# untitled.net
KiCad netlist of a schematic drawn in EAGLE
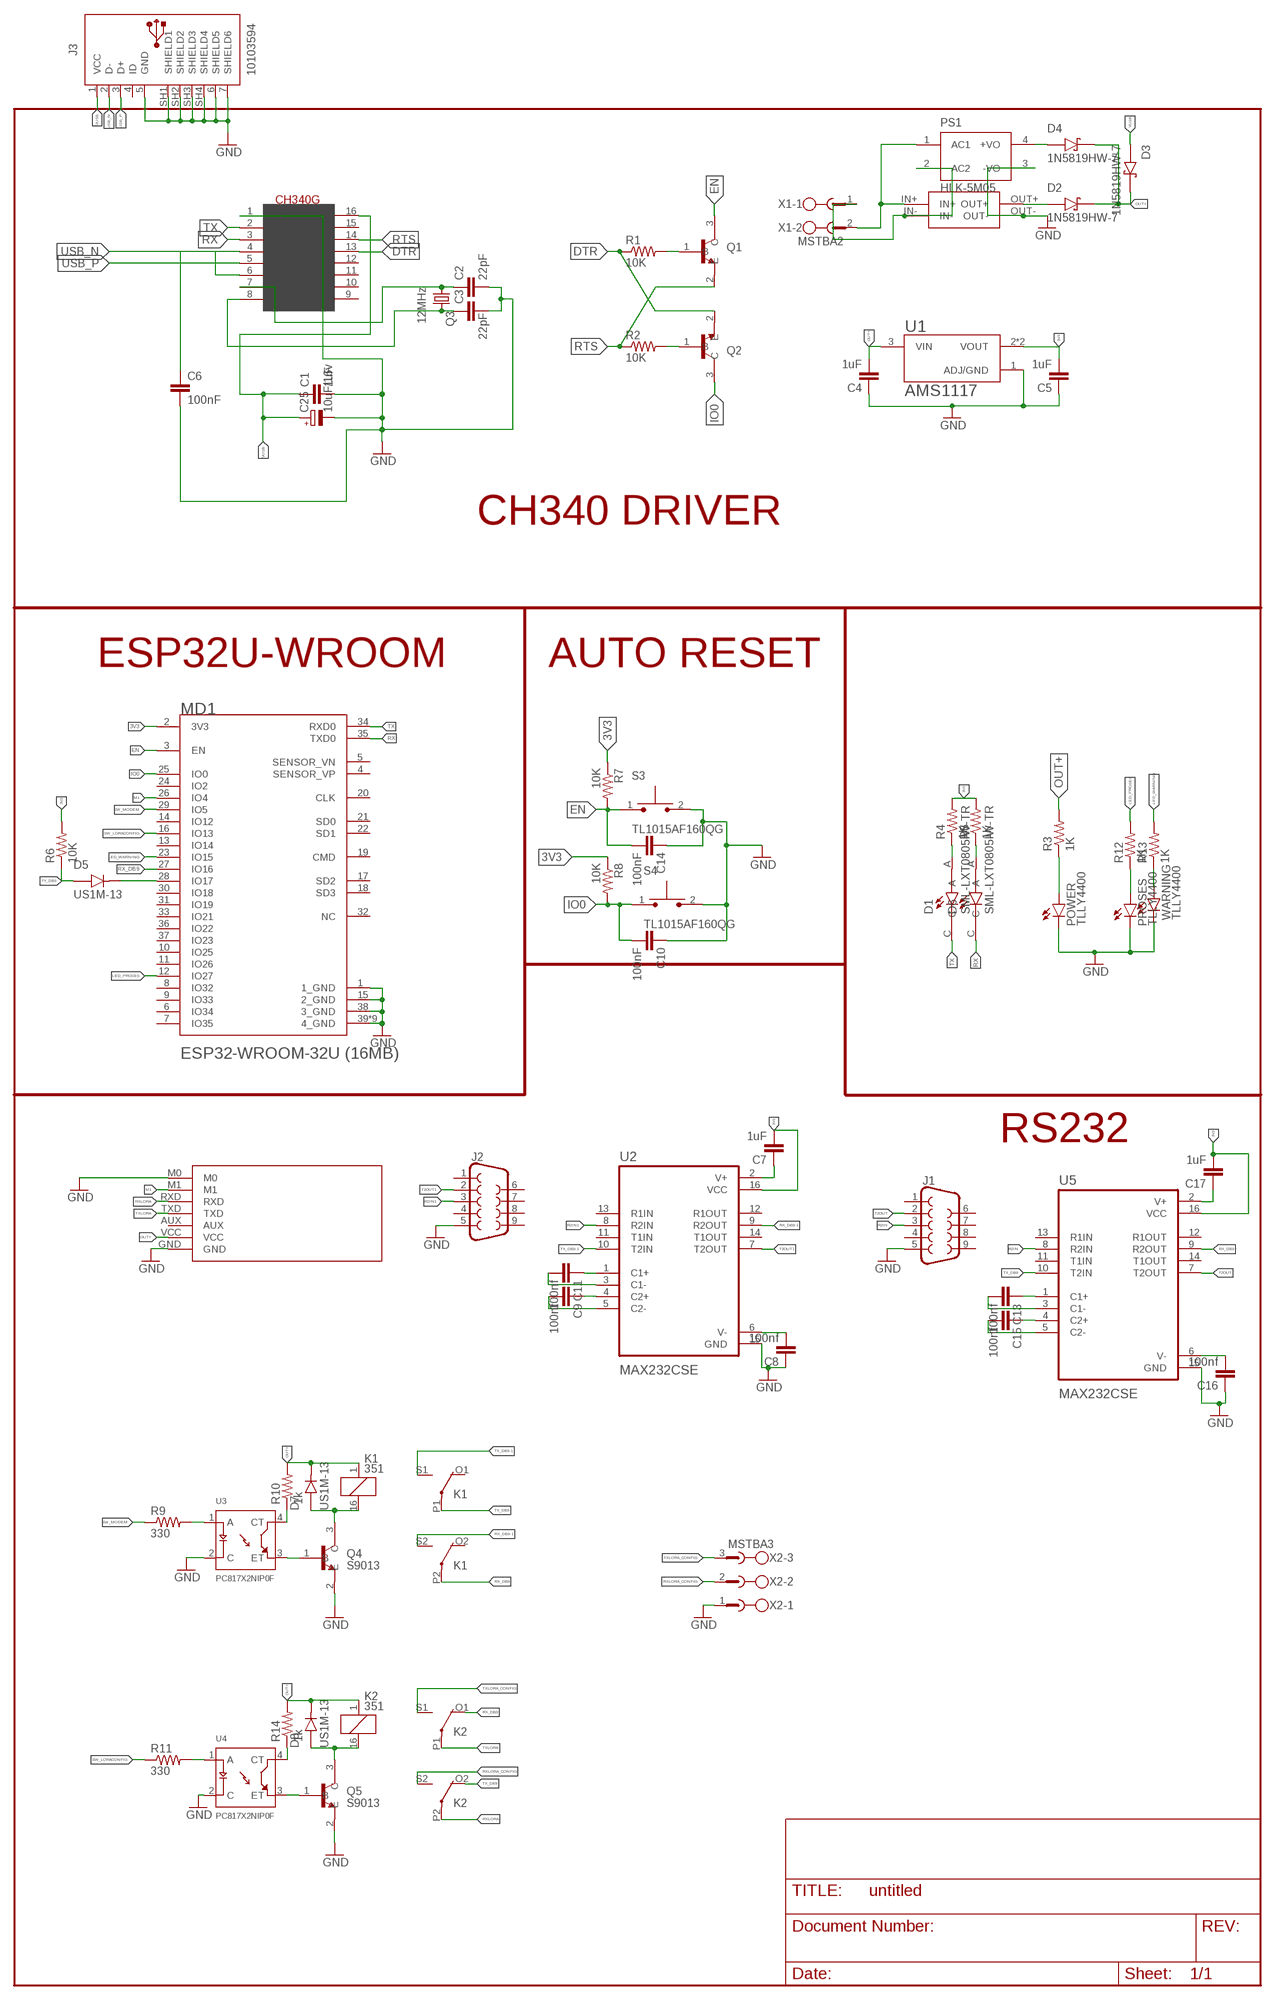
[diagram p0: schematic, sheet 1]

(export (version "E")
  (design (tool "Eeschema 10.0.6"))
  (components
    (comp (ref "C1")
      (value "1uF")
      (footprint "eagle-import:C0805K")
      (libsource (lib "eagle-import") (part "C-EUC0805K"))
    )
    (comp (ref "C2")
      (value "22pF")
      (footprint "eagle-import:C0805K")
      (libsource (lib "eagle-import") (part "C-EUC0805K"))
    )
    (comp (ref "C3")
      (value "22pF")
      (footprint "eagle-import:C0805K")
      (libsource (lib "eagle-import") (part "C-EUC0805K"))
    )
    (comp (ref "C4")
      (value "1uF")
      (footprint "eagle-import:C0805K")
      (libsource (lib "eagle-import") (part "C-EUC0805K"))
    )
    (comp (ref "C5")
      (value "1uF")
      (footprint "eagle-import:C0805K")
      (libsource (lib "eagle-import") (part "C-EUC0805K"))
    )
    (comp (ref "C6")
      (value "100nF")
      (footprint "eagle-import:C0805K")
      (libsource (lib "eagle-import") (part "C-EUC0805K"))
    )
    (comp (ref "C7")
      (value "1uF")
      (footprint "eagle-import:C0805")
      (libsource (lib "eagle-import") (part "C-EUC0805"))
    )
    (comp (ref "C8")
      (value "100nf")
      (footprint "eagle-import:C0805")
      (libsource (lib "eagle-import") (part "C-EUC0805"))
    )
    (comp (ref "C9")
      (value "100nf")
      (footprint "eagle-import:C0805")
      (libsource (lib "eagle-import") (part "C-EUC0805"))
    )
    (comp (ref "C10")
      (value "100nF")
      (footprint "eagle-import:C0805K")
      (libsource (lib "eagle-import") (part "C-EUC0805K"))
    )
    (comp (ref "C11")
      (value "100nf")
      (footprint "eagle-import:C0805")
      (libsource (lib "eagle-import") (part "C-EUC0805"))
    )
    (comp (ref "C13")
      (value "100nf")
      (footprint "eagle-import:C0805")
      (libsource (lib "eagle-import") (part "C-EUC0805"))
    )
    (comp (ref "C14")
      (value "100nF")
      (footprint "eagle-import:C0805K")
      (libsource (lib "eagle-import") (part "C-EUC0805K"))
    )
    (comp (ref "C15")
      (value "100nf")
      (footprint "eagle-import:C0805")
      (libsource (lib "eagle-import") (part "C-EUC0805"))
    )
    (comp (ref "C16")
      (value "100nf")
      (footprint "eagle-import:C0805")
      (libsource (lib "eagle-import") (part "C-EUC0805"))
    )
    (comp (ref "C17")
      (value "1uF")
      (footprint "eagle-import:C0805")
      (libsource (lib "eagle-import") (part "C-EUC0805"))
    )
    (comp (ref "C25")
      (value "10uF/16v")
      (footprint "eagle-import:153CLV-0505")
      (libsource (lib "eagle-import") (part "CPOL-EU153CLV-0505"))
    )
    (comp (ref "D1")
      (value "SML-LXT0805IW-TR")
      (footprint "eagle-import:LEDC2012X120N")
      (fields (field (name "MF") "Lumex Opto/Components"))
      (libsource (lib "eagle-import") (part "SML-LXT0805IW-TR"))
    )
    (comp (ref "D2")
      (value "1N5819HW-7")
      (footprint "eagle-import:SOD3715X145N")
      (fields (field (name "MF") "Diodes Inc."))
      (libsource (lib "eagle-import") (part "1N5819HW-7"))
    )
    (comp (ref "D3")
      (value "1N5819HW-7")
      (footprint "eagle-import:SOD3715X145N")
      (fields (field (name "MF") "Diodes Inc."))
      (libsource (lib "eagle-import") (part "1N5819HW-7"))
    )
    (comp (ref "D4")
      (value "1N5819HW-7")
      (footprint "eagle-import:SOD3715X145N")
      (fields (field (name "MF") "Diodes Inc."))
      (libsource (lib "eagle-import") (part "1N5819HW-7"))
    )
    (comp (ref "D5")
      (value "US1M-13")
      (footprint "eagle-import:DIOM5226X240N")
      (fields (field (name "MF") "Diodes Incorporated"))
      (libsource (lib "eagle-import") (part "US1M-13"))
    )
    (comp (ref "D6")
      (value "SML-LXT0805IW-TR")
      (footprint "eagle-import:LEDC2012X120N")
      (fields (field (name "MF") "Lumex Opto/Components"))
      (libsource (lib "eagle-import") (part "SML-LXT0805IW-TR"))
    )
    (comp (ref "D7")
      (value "US1M-13")
      (footprint "eagle-import:DIOM5226X240N")
      (fields (field (name "MF") "Diodes Incorporated"))
      (libsource (lib "eagle-import") (part "US1M-13"))
    )
    (comp (ref "D8")
      (value "US1M-13")
      (footprint "eagle-import:DIOM5226X240N")
      (fields (field (name "MF") "Diodes Incorporated"))
      (libsource (lib "eagle-import") (part "US1M-13"))
    )
    (comp (ref "EBYTEE220-900T22D1")
      (value "EBYTEE220-900T22D")
      (footprint "eagle-import:EBYTEE220-900T22D")
      (libsource (lib "eagle-import") (part "EBYTEE220-900T22D"))
    )
    (comp (ref "J1")
      (value "DB9MALE")
      (footprint "eagle-import:DB9_MALE")
      (libsource (lib "eagle-import") (part "DB9MALE"))
    )
    (comp (ref "J2")
      (value "DB9MALE")
      (footprint "eagle-import:DB9_MALE")
      (libsource (lib "eagle-import") (part "DB9MALE"))
    )
    (comp (ref "J3")
      (value "10103594")
      (footprint "eagle-import:10103594")
      (fields (field (name "MANUFACTURER") "Amphenol ICC (FCI)") (field (name "MPN") "10103594-0001LF"))
      (libsource (lib "eagle-import") (part "10103594"))
    )
    (comp (ref "K1")
      (value "351")
      (footprint "eagle-import:351")
      (libsource (lib "eagle-import") (part "351"))
    )
    (comp (ref "K2")
      (value "351")
      (footprint "eagle-import:351")
      (libsource (lib "eagle-import") (part "351"))
    )
    (comp (ref "MD1")
      (value "ESPRESSIF_SYSTEMS_ESP32-WROOM-32U_16MBESPRESSIF_SYSTEMS_ESP32-WROOM-32U_16MB_0_0")
      (footprint "eagle-import:ESPRESSIF_SYSTEMS_ESP32-WROOM-32U_16MB_0")
      (fields
        (field (name "DIGIKEY_PART_NUMBER") "1904-1028-1-ND")
        (field (name "MF") "Espressif Systems")
        (field (name "MOUSER_PART_NUMBER") "356-ES32WROOM32U16MB")
      )
      (libsource (lib "eagle-import") (part "ESPRESSIF_SYSTEMS_ESP32-WROOM-32U_16MBESPRESSIF_SYSTEMS_ESP32-WROOM-32U_16MB_0_0"))
    )
    (comp (ref "MINI1")
      (value "MINI560")
      (footprint "eagle-import:MINI560")
      (libsource (lib "eagle-import") (part "MINI560"))
    )
    (comp (ref "POWER")
      (value "TLLY4400")
      (footprint "eagle-import:LED3MM")
      (fields (field (name "MF") "VISHAY SEMICONDUCTOR"))
      (libsource (lib "eagle-import") (part "TLLY4400"))
    )
    (comp (ref "PROSES")
      (value "TLLY4400")
      (footprint "eagle-import:LED3MM")
      (fields (field (name "MF") "VISHAY SEMICONDUCTOR"))
      (libsource (lib "eagle-import") (part "TLLY4400"))
    )
    (comp (ref "PS1")
      (value "HLK-5M05")
      (footprint "eagle-import:CONV_HLK-5M05")
      (fields (field (name "MF") "Hi-link"))
      (libsource (lib "eagle-import") (part "HLK-5M05"))
    )
    (comp (ref "Q1")
      (value "MMBT3904")
      (footprint "eagle-import:SOT95P240X120-3N")
      (fields (field (name "MF") "STMicroelectronics"))
      (libsource (lib "eagle-import") (part "MMBT3904"))
    )
    (comp (ref "Q2")
      (value "MMBT3904")
      (footprint "eagle-import:SOT95P240X120-3N")
      (fields (field (name "MF") "STMicroelectronics"))
      (libsource (lib "eagle-import") (part "MMBT3904"))
    )
    (comp (ref "Q3")
      (value "12MHz")
      (footprint "eagle-import:SM49")
      (libsource (lib "eagle-import") (part "CRYSTALSM49"))
    )
    (comp (ref "Q4")
      (value "S9013")
      (footprint "eagle-import:SOT95P240X120-3N")
      (fields (field (name "MF") "JCET"))
      (libsource (lib "eagle-import") (part "S9013"))
    )
    (comp (ref "Q5")
      (value "S9013")
      (footprint "eagle-import:SOT95P240X120-3N")
      (fields (field (name "MF") "JCET"))
      (libsource (lib "eagle-import") (part "S9013"))
    )
    (comp (ref "R1")
      (value "10K")
      (footprint "eagle-import:M0805")
      (libsource (lib "eagle-import") (part "R-US_M0805"))
    )
    (comp (ref "R2")
      (value "10K")
      (footprint "eagle-import:M0805")
      (libsource (lib "eagle-import") (part "R-US_M0805"))
    )
    (comp (ref "R3")
      (value "1K")
      (footprint "eagle-import:M0805")
      (libsource (lib "eagle-import") (part "R-US_M0805"))
    )
    (comp (ref "R4")
      (value "1K")
      (footprint "eagle-import:M0805")
      (libsource (lib "eagle-import") (part "R-US_M0805"))
    )
    (comp (ref "R5")
      (value "1K")
      (footprint "eagle-import:M0805")
      (libsource (lib "eagle-import") (part "R-US_M0805"))
    )
    (comp (ref "R6")
      (value "10K")
      (footprint "eagle-import:M0805")
      (libsource (lib "eagle-import") (part "R-US_M0805"))
    )
    (comp (ref "R7")
      (value "10K")
      (footprint "eagle-import:M0805")
      (libsource (lib "eagle-import") (part "R-US_M0805"))
    )
    (comp (ref "R8")
      (value "10K")
      (footprint "eagle-import:M0805")
      (libsource (lib "eagle-import") (part "R-US_M0805"))
    )
    (comp (ref "R9")
      (value "330")
      (footprint "eagle-import:M0805")
      (libsource (lib "eagle-import") (part "R-US_M0805"))
    )
    (comp (ref "R10")
      (value "1k")
      (footprint "eagle-import:M0805")
      (libsource (lib "eagle-import") (part "R-US_M0805"))
    )
    (comp (ref "R11")
      (value "330")
      (footprint "eagle-import:M0805")
      (libsource (lib "eagle-import") (part "R-US_M0805"))
    )
    (comp (ref "R12")
      (value "1K")
      (footprint "eagle-import:M0805")
      (libsource (lib "eagle-import") (part "R-US_M0805"))
    )
    (comp (ref "R13")
      (value "1K")
      (footprint "eagle-import:M0805")
      (libsource (lib "eagle-import") (part "R-US_M0805"))
    )
    (comp (ref "R14")
      (value "1k")
      (footprint "eagle-import:M0805")
      (libsource (lib "eagle-import") (part "R-US_M0805"))
    )
    (comp (ref "S3")
      (value "TL1015AF160QG")
      (footprint "eagle-import:SW_TL1015AF160QG")
      (fields (field (name "MF") "E-Switch"))
      (libsource (lib "eagle-import") (part "TL1015AF160QG"))
    )
    (comp (ref "S4")
      (value "TL1015AF160QG")
      (footprint "eagle-import:SW_TL1015AF160QG")
      (fields (field (name "MF") "E-Switch"))
      (libsource (lib "eagle-import") (part "TL1015AF160QG"))
    )
    (comp (ref "U$2")
      (value "CH340G")
      (footprint "eagle-import:SOIC16")
      (libsource (lib "eagle-import") (part "CH340G"))
    )
    (comp (ref "U1")
      (value "AMS1117")
      (footprint "eagle-import:SOT229P700X180-4N")
      (fields (field (name "MF") "Advanced Monolithic Systems"))
      (libsource (lib "eagle-import") (part "AMS1117"))
    )
    (comp (ref "U2")
      (value "MAX232CSE")
      (footprint "eagle-import:SOIC127P600X175-16N")
      (fields (field (name "MF") "Maxim Integrated"))
      (libsource (lib "eagle-import") (part "MAX232CSE"))
    )
    (comp (ref "U3")
      (value "PC817X2NIP0F")
      (footprint "eagle-import:SOT254P975X400-4N")
      (fields (field (name "MF") "Sharp Microelectronics"))
      (libsource (lib "eagle-import") (part "PC817X2NIP0F"))
    )
    (comp (ref "U4")
      (value "PC817X2NIP0F")
      (footprint "eagle-import:SOT254P975X400-4N")
      (fields (field (name "MF") "Sharp Microelectronics"))
      (libsource (lib "eagle-import") (part "PC817X2NIP0F"))
    )
    (comp (ref "U5")
      (value "MAX232CSE")
      (footprint "eagle-import:SOIC127P600X175-16N")
      (fields (field (name "MF") "Maxim Integrated"))
      (libsource (lib "eagle-import") (part "MAX232CSE"))
    )
    (comp (ref "WARNING")
      (value "TLLY4400")
      (footprint "eagle-import:LED3MM")
      (fields (field (name "MF") "VISHAY SEMICONDUCTOR"))
      (libsource (lib "eagle-import") (part "TLLY4400"))
    )
    (comp (ref "X1")
      (value "MSTBA2")
      (footprint "eagle-import:MSTBA2")
      (fields (field (name "MF") "FARNELL") (field (name "MPN") "1757242"))
      (libsource (lib "eagle-import") (part "MSTBA2"))
    )
    (comp (ref "X2")
      (value "MSTBA3")
      (footprint "eagle-import:MSTBA3")
      (fields (field (name "MF") "FARNELL") (field (name "MPN") "1757255"))
      (libsource (lib "eagle-import") (part "MSTBA3"))
    )
  )
  (nets
    (net (code "1") (name "3V3") (class "Default")
      (node (ref "C17") (pin "2") (pinfunction "2_2") (pintype "passive"))
      (node (ref "C5") (pin "2") (pinfunction "2_2") (pintype "passive"))
      (node (ref "C7") (pin "2") (pinfunction "2_2") (pintype "passive"))
      (node (ref "MD1") (pin "2") (pinfunction "3V3_2") (pintype "power_in"))
      (node (ref "R4") (pin "2") (pinfunction "2_2") (pintype "passive"))
      (node (ref "R5") (pin "2") (pinfunction "2_2") (pintype "passive"))
      (node (ref "R6") (pin "2") (pinfunction "2_2") (pintype "passive"))
      (node (ref "R7") (pin "1") (pinfunction "1_1") (pintype "passive"))
      (node (ref "R8") (pin "1") (pinfunction "1_1") (pintype "passive"))
      (node (ref "U1") (pin "2") (pinfunction "VOUT_2") (pintype "output"))
      (node (ref "U1") (pin "4") (pinfunction "VOUT_4") (pintype "output"))
      (node (ref "U2") (pin "16") (pinfunction "VCC_16") (pintype "power_in"))
      (node (ref "U5") (pin "16") (pinfunction "VCC_16") (pintype "power_in"))
    )
    (net (code "2") (name "DTR") (class "Default")
      (node (ref "Q2") (pin "2") (pinfunction "E_2") (pintype "passive"))
      (node (ref "R1") (pin "1") (pinfunction "1_1") (pintype "passive"))
      (node (ref "U$2") (pin "13") (pinfunction "DTR_13") (pintype "bidirectional"))
    )
    (net (code "3") (name "EN") (class "Default")
      (node (ref "C14") (pin "2") (pinfunction "2_2") (pintype "passive"))
      (node (ref "MD1") (pin "3") (pinfunction "EN_3") (pintype "input"))
      (node (ref "Q1") (pin "3") (pinfunction "C_3") (pintype "passive"))
      (node (ref "R7") (pin "2") (pinfunction "2_2") (pintype "passive"))
      (node (ref "S3") (pin "1") (pinfunction "1_1") (pintype "passive"))
    )
    (net (code "4") (name "GND") (class "Default")
      (node (ref "C1") (pin "2") (pinfunction "2_2") (pintype "passive"))
      (node (ref "C10") (pin "1") (pinfunction "1_1") (pintype "passive"))
      (node (ref "C14") (pin "1") (pinfunction "1_1") (pintype "passive"))
      (node (ref "C16") (pin "1") (pinfunction "1_1") (pintype "passive"))
      (node (ref "C2") (pin "2") (pinfunction "2_2") (pintype "passive"))
      (node (ref "C25") (pin "-") (pinfunction "-_-") (pintype "passive"))
      (node (ref "C3") (pin "2") (pinfunction "2_2") (pintype "passive"))
      (node (ref "C4") (pin "1") (pinfunction "1_1") (pintype "passive"))
      (node (ref "C5") (pin "1") (pinfunction "1_1") (pintype "passive"))
      (node (ref "C6") (pin "2") (pinfunction "2_2") (pintype "passive"))
      (node (ref "C8") (pin "1") (pinfunction "1_1") (pintype "passive"))
      (node (ref "EBYTEE220-900T22D1") (pin "GND") (pinfunction "GND_GND") (pintype "bidirectional"))
      (node (ref "EBYTEE220-900T22D1") (pin "M0") (pinfunction "M0_M0") (pintype "bidirectional"))
      (node (ref "J1") (pin "5") (pinfunction "5_5") (pintype "passive"))
      (node (ref "J2") (pin "5") (pinfunction "5_5") (pintype "passive"))
      (node (ref "J3") (pin "5") (pinfunction "GND_5") (pintype "power_in"))
      (node (ref "J3") (pin "6") (pinfunction "SHIELD5_6") (pintype "power_in"))
      (node (ref "J3") (pin "7") (pinfunction "SHIELD6_7") (pintype "power_in"))
      (node (ref "J3") (pin "SH1") (pinfunction "SHIELD1_SH1") (pintype "power_in"))
      (node (ref "J3") (pin "SH2") (pinfunction "SHIELD2_SH2") (pintype "power_in"))
      (node (ref "J3") (pin "SH3") (pinfunction "SHIELD3_SH3") (pintype "power_in"))
      (node (ref "J3") (pin "SH4") (pinfunction "SHIELD4_SH4") (pintype "power_in"))
      (node (ref "MD1") (pin "1") (pinfunction "1_GND_1") (pintype "power_in"))
      (node (ref "MD1") (pin "15") (pinfunction "2_GND_15") (pintype "power_in"))
      (node (ref "MD1") (pin "38") (pinfunction "3_GND_38") (pintype "power_in"))
      (node (ref "MD1") (pin "39") (pinfunction "4_GND_39") (pintype "power_in"))
      (node (ref "MD1") (pin "39-2") (pinfunction "4_GND_39-2") (pintype "power_in"))
      (node (ref "MD1") (pin "39-3") (pinfunction "4_GND_39-3") (pintype "power_in"))
      (node (ref "MD1") (pin "39-4") (pinfunction "4_GND_39-4") (pintype "power_in"))
      (node (ref "MD1") (pin "39-5") (pinfunction "4_GND_39-5") (pintype "power_in"))
      (node (ref "MD1") (pin "39-6") (pinfunction "4_GND_39-6") (pintype "power_in"))
      (node (ref "MD1") (pin "39-7") (pinfunction "4_GND_39-7") (pintype "power_in"))
      (node (ref "MD1") (pin "39-8") (pinfunction "4_GND_39-8") (pintype "power_in"))
      (node (ref "MD1") (pin "39-9") (pinfunction "4_GND_39-9") (pintype "power_in"))
      (node (ref "MINI1") (pin "OUT-") (pinfunction "OUT-_OUT-") (pintype "bidirectional"))
      (node (ref "POWER") (pin "K") (pinfunction "C_K") (pintype "passive"))
      (node (ref "PROSES") (pin "K") (pinfunction "C_K") (pintype "passive"))
      (node (ref "PS1") (pin "3") (pinfunction "-VO_3") (pintype "output"))
      (node (ref "Q4") (pin "2") (pinfunction "E_2") (pintype "passive"))
      (node (ref "Q5") (pin "2") (pinfunction "E_2") (pintype "passive"))
      (node (ref "S3") (pin "2") (pinfunction "2_2") (pintype "passive"))
      (node (ref "S4") (pin "2") (pinfunction "2_2") (pintype "passive"))
      (node (ref "U$2") (pin "1") (pinfunction "GND_1") (pintype "bidirectional"))
      (node (ref "U1") (pin "1") (pinfunction "ADJ/GND_1") (pintype "power_in"))
      (node (ref "U2") (pin "15") (pinfunction "GND_15") (pintype "power_in"))
      (node (ref "U3") (pin "2") (pinfunction "C_2") (pintype "passive"))
      (node (ref "U4") (pin "2") (pinfunction "C_2") (pintype "passive"))
      (node (ref "U5") (pin "15") (pinfunction "GND_15") (pintype "power_in"))
      (node (ref "WARNING") (pin "K") (pinfunction "C_K") (pintype "passive"))
      (node (ref "X2") (pin "1") (pinfunction "1_1") (pintype "passive"))
    )
    (net (code "5") (name "IO0") (class "Default")
      (node (ref "C10") (pin "2") (pinfunction "2_2") (pintype "passive"))
      (node (ref "MD1") (pin "25") (pinfunction "IO0_25") (pintype "bidirectional"))
      (node (ref "Q2") (pin "3") (pinfunction "C_3") (pintype "passive"))
      (node (ref "R8") (pin "2") (pinfunction "2_2") (pintype "passive"))
      (node (ref "S4") (pin "1") (pinfunction "1_1") (pintype "passive"))
    )
    (net (code "6") (name "LED_PROSES") (class "Default")
      (node (ref "MD1") (pin "12") (pinfunction "IO27_12") (pintype "bidirectional"))
      (node (ref "R12") (pin "2") (pinfunction "2_2") (pintype "passive"))
    )
    (net (code "7") (name "LED_WARNING") (class "Default")
      (node (ref "MD1") (pin "23") (pinfunction "IO15_23") (pintype "bidirectional"))
      (node (ref "R13") (pin "2") (pinfunction "2_2") (pintype "passive"))
    )
    (net (code "8") (name "M1") (class "Default")
      (node (ref "EBYTEE220-900T22D1") (pin "M1") (pinfunction "M1_M1") (pintype "bidirectional"))
      (node (ref "MD1") (pin "26") (pinfunction "IO4_26") (pintype "bidirectional"))
    )
    (net (code "9") (name "Net-(D1-PadA)") (class "Default")
      (node (ref "D1") (pin "A") (pinfunction "A_A") (pintype "passive"))
      (node (ref "R4") (pin "1") (pinfunction "1_1") (pintype "passive"))
    )
    (net (code "10") (name "Net-(D2-PadA)") (class "Default")
      (node (ref "D2") (pin "A") (pinfunction "A_A") (pintype "passive"))
      (node (ref "MINI1") (pin "OUT+") (pinfunction "OUT+_OUT+") (pintype "bidirectional"))
    )
    (net (code "11") (name "Net-(D5-K)") (class "Default")
      (node (ref "D5") (pin "C") (pinfunction "K_C") (pintype "passive"))
      (node (ref "MD1") (pin "28") (pinfunction "IO17_28") (pintype "bidirectional"))
    )
    (net (code "12") (name "Net-(D6-PadA)") (class "Default")
      (node (ref "D6") (pin "A") (pinfunction "A_A") (pintype "passive"))
      (node (ref "R5") (pin "1") (pinfunction "1_1") (pintype "passive"))
    )
    (net (code "13") (name "Net-(K1A-2)") (class "Default")
      (node (ref "D7") (pin "A") (pinfunction "A_A") (pintype "passive"))
      (node (ref "K1") (pin "16") (pinfunction "2_16") (pintype "passive"))
      (node (ref "Q4") (pin "3") (pinfunction "C_3") (pintype "passive"))
    )
    (net (code "14") (name "Net-(K2A-2)") (class "Default")
      (node (ref "D8") (pin "A") (pinfunction "A_A") (pintype "passive"))
      (node (ref "K2") (pin "16") (pinfunction "2_16") (pintype "passive"))
      (node (ref "Q5") (pin "3") (pinfunction "C_3") (pintype "passive"))
    )
    (net (code "15") (name "Net-(POWER-PadA)") (class "Default")
      (node (ref "POWER") (pin "A") (pinfunction "A_A") (pintype "passive"))
      (node (ref "R3") (pin "1") (pinfunction "1_1") (pintype "passive"))
    )
    (net (code "16") (name "Net-(PROSES-PadA)") (class "Default")
      (node (ref "PROSES") (pin "A") (pinfunction "A_A") (pintype "passive"))
      (node (ref "R12") (pin "1") (pinfunction "1_1") (pintype "passive"))
    )
    (net (code "17") (name "Net-(PS1-+VO)") (class "Default")
      (node (ref "D4") (pin "A") (pinfunction "A_A") (pintype "passive"))
      (node (ref "PS1") (pin "4") (pinfunction "+VO_4") (pintype "output"))
    )
    (net (code "18") (name "Net-(PS1-AC1)") (class "Default")
      (node (ref "MINI1") (pin "IN+") (pinfunction "IN+_IN+") (pintype "bidirectional"))
      (node (ref "PS1") (pin "1") (pinfunction "AC1_1") (pintype "input"))
      (node (ref "X1") (pin "2") (pinfunction "1_2") (pintype "passive"))
    )
    (net (code "19") (name "Net-(PS1-AC2)") (class "Default")
      (node (ref "MINI1") (pin "IN-") (pinfunction "IN-_IN-") (pintype "bidirectional"))
      (node (ref "PS1") (pin "2") (pinfunction "AC2_2") (pintype "input"))
      (node (ref "X1") (pin "1") (pinfunction "1_1") (pintype "passive"))
    )
    (net (code "20") (name "Net-(Q1-B)") (class "Default")
      (node (ref "Q1") (pin "1") (pinfunction "B_1") (pintype "passive"))
      (node (ref "R1") (pin "2") (pinfunction "2_2") (pintype "passive"))
    )
    (net (code "21") (name "Net-(Q2-B)") (class "Default")
      (node (ref "Q2") (pin "1") (pinfunction "B_1") (pintype "passive"))
      (node (ref "R2") (pin "2") (pinfunction "2_2") (pintype "passive"))
    )
    (net (code "22") (name "Net-(Q4-B)") (class "Default")
      (node (ref "Q4") (pin "1") (pinfunction "B_1") (pintype "passive"))
      (node (ref "U3") (pin "3") (pinfunction "ET_3") (pintype "passive"))
    )
    (net (code "23") (name "Net-(Q5-B)") (class "Default")
      (node (ref "Q5") (pin "1") (pinfunction "B_1") (pintype "passive"))
      (node (ref "U4") (pin "3") (pinfunction "ET_3") (pintype "passive"))
    )
    (net (code "24") (name "Net-(R13-Pad1)") (class "Default")
      (node (ref "R13") (pin "1") (pinfunction "1_1") (pintype "passive"))
      (node (ref "WARNING") (pin "A") (pinfunction "A_A") (pintype "passive"))
    )
    (net (code "25") (name "Net-(U$2-V3)") (class "Default")
      (node (ref "C6") (pin "1") (pinfunction "1_1") (pintype "passive"))
      (node (ref "U$2") (pin "4") (pinfunction "V3_4") (pintype "bidirectional"))
    )
    (net (code "26") (name "Net-(U$2-XI)") (class "Default")
      (node (ref "C2") (pin "1") (pinfunction "1_1") (pintype "passive"))
      (node (ref "Q3") (pin "1") (pinfunction "1_1") (pintype "passive"))
      (node (ref "U$2") (pin "7") (pinfunction "XI_7") (pintype "bidirectional"))
    )
    (net (code "27") (name "Net-(U$2-XO)") (class "Default")
      (node (ref "C3") (pin "1") (pinfunction "1_1") (pintype "passive"))
      (node (ref "Q3") (pin "2") (pinfunction "2_2") (pintype "passive"))
      (node (ref "U$2") (pin "8") (pinfunction "XO_8") (pintype "bidirectional"))
    )
    (net (code "28") (name "Net-(U2-C1+)") (class "Default")
      (node (ref "C11") (pin "1") (pinfunction "1_1") (pintype "passive"))
      (node (ref "U2") (pin "1") (pinfunction "C1+_1") (pintype "bidirectional"))
    )
    (net (code "29") (name "Net-(U2-C1-)") (class "Default")
      (node (ref "C11") (pin "2") (pinfunction "2_2") (pintype "passive"))
      (node (ref "U2") (pin "3") (pinfunction "C1-_3") (pintype "bidirectional"))
    )
    (net (code "30") (name "Net-(U2-C2+)") (class "Default")
      (node (ref "C9") (pin "1") (pinfunction "1_1") (pintype "passive"))
      (node (ref "U2") (pin "4") (pinfunction "C2+_4") (pintype "bidirectional"))
    )
    (net (code "31") (name "Net-(U2-C2-)") (class "Default")
      (node (ref "C9") (pin "2") (pinfunction "2_2") (pintype "passive"))
      (node (ref "U2") (pin "5") (pinfunction "C2-_5") (pintype "bidirectional"))
    )
    (net (code "32") (name "Net-(U2-V+)") (class "Default")
      (node (ref "C7") (pin "1") (pinfunction "1_1") (pintype "passive"))
      (node (ref "U2") (pin "2") (pinfunction "V+_2") (pintype "power_in"))
    )
    (net (code "33") (name "Net-(U2-V-)") (class "Default")
      (node (ref "C8") (pin "2") (pinfunction "2_2") (pintype "passive"))
      (node (ref "U2") (pin "6") (pinfunction "V-_6") (pintype "power_in"))
    )
    (net (code "34") (name "Net-(U3-A)") (class "Default")
      (node (ref "R9") (pin "2") (pinfunction "2_2") (pintype "passive"))
      (node (ref "U3") (pin "1") (pinfunction "A_1") (pintype "passive"))
    )
    (net (code "35") (name "Net-(U3-CT)") (class "Default")
      (node (ref "R10") (pin "1") (pinfunction "1_1") (pintype "passive"))
      (node (ref "U3") (pin "4") (pinfunction "CT_4") (pintype "passive"))
    )
    (net (code "36") (name "Net-(U4-A)") (class "Default")
      (node (ref "R11") (pin "2") (pinfunction "2_2") (pintype "passive"))
      (node (ref "U4") (pin "1") (pinfunction "A_1") (pintype "passive"))
    )
    (net (code "37") (name "Net-(U4-CT)") (class "Default")
      (node (ref "R14") (pin "1") (pinfunction "1_1") (pintype "passive"))
      (node (ref "U4") (pin "4") (pinfunction "CT_4") (pintype "passive"))
    )
    (net (code "38") (name "Net-(U5-C1+)") (class "Default")
      (node (ref "C13") (pin "1") (pinfunction "1_1") (pintype "passive"))
      (node (ref "U5") (pin "1") (pinfunction "C1+_1") (pintype "bidirectional"))
    )
    (net (code "39") (name "Net-(U5-C1-)") (class "Default")
      (node (ref "C13") (pin "2") (pinfunction "2_2") (pintype "passive"))
      (node (ref "U5") (pin "3") (pinfunction "C1-_3") (pintype "bidirectional"))
    )
    (net (code "40") (name "Net-(U5-C2+)") (class "Default")
      (node (ref "C15") (pin "1") (pinfunction "1_1") (pintype "passive"))
      (node (ref "U5") (pin "4") (pinfunction "C2+_4") (pintype "bidirectional"))
    )
    (net (code "41") (name "Net-(U5-C2-)") (class "Default")
      (node (ref "C15") (pin "2") (pinfunction "2_2") (pintype "passive"))
      (node (ref "U5") (pin "5") (pinfunction "C2-_5") (pintype "bidirectional"))
    )
    (net (code "42") (name "Net-(U5-V+)") (class "Default")
      (node (ref "C17") (pin "1") (pinfunction "1_1") (pintype "passive"))
      (node (ref "U5") (pin "2") (pinfunction "V+_2") (pintype "power_in"))
    )
    (net (code "43") (name "Net-(U5-V-)") (class "Default")
      (node (ref "C16") (pin "2") (pinfunction "2_2") (pintype "passive"))
      (node (ref "U5") (pin "6") (pinfunction "V-_6") (pintype "power_in"))
    )
    (net (code "44") (name "OUT+") (class "Default")
      (node (ref "C4") (pin "2") (pinfunction "2_2") (pintype "passive"))
      (node (ref "D2") (pin "C") (pinfunction "K_C") (pintype "passive"))
      (node (ref "D3") (pin "C") (pinfunction "K_C") (pintype "passive"))
      (node (ref "D4") (pin "C") (pinfunction "K_C") (pintype "passive"))
      (node (ref "D7") (pin "C") (pinfunction "K_C") (pintype "passive"))
      (node (ref "D8") (pin "C") (pinfunction "K_C") (pintype "passive"))
      (node (ref "EBYTEE220-900T22D1") (pin "VCC") (pinfunction "VCC_VCC") (pintype "bidirectional"))
      (node (ref "K1") (pin "1") (pinfunction "1_1") (pintype "passive"))
      (node (ref "K2") (pin "1") (pinfunction "1_1") (pintype "passive"))
      (node (ref "R10") (pin "2") (pinfunction "2_2") (pintype "passive"))
      (node (ref "R14") (pin "2") (pinfunction "2_2") (pintype "passive"))
      (node (ref "R3") (pin "2") (pinfunction "2_2") (pintype "passive"))
      (node (ref "U1") (pin "3") (pinfunction "VIN_3") (pintype "input"))
    )
    (net (code "45") (name "R2IN") (class "Default")
      (node (ref "J1") (pin "3") (pinfunction "3_3") (pintype "passive"))
      (node (ref "U5") (pin "8") (pinfunction "R2IN_8") (pintype "input"))
    )
    (net (code "46") (name "R2IN1") (class "Default")
      (node (ref "J2") (pin "3") (pinfunction "3_3") (pintype "passive"))
      (node (ref "U2") (pin "8") (pinfunction "R2IN_8") (pintype "input"))
    )
    (net (code "47") (name "RTS") (class "Default")
      (node (ref "Q1") (pin "2") (pinfunction "E_2") (pintype "passive"))
      (node (ref "R2") (pin "1") (pinfunction "1_1") (pintype "passive"))
      (node (ref "U$2") (pin "14") (pinfunction "RTS_14") (pintype "bidirectional"))
    )
    (net (code "48") (name "RX") (class "Default")
      (node (ref "D6") (pin "C") (pinfunction "C_C") (pintype "passive"))
      (node (ref "MD1") (pin "35") (pinfunction "TXD0_35") (pintype "bidirectional"))
      (node (ref "U$2") (pin "3") (pinfunction "RX_3") (pintype "bidirectional"))
    )
    (net (code "49") (name "RXLORA") (class "Default")
      (node (ref "EBYTEE220-900T22D1") (pin "RXD") (pinfunction "RXD_RXD") (pintype "bidirectional"))
      (node (ref "K2") (pin "P2") (pinfunction "P_P2") (pintype "passive"))
    )
    (net (code "50") (name "RXLORA_CONFIG") (class "Default")
      (node (ref "K2") (pin "S2") (pinfunction "S_S2") (pintype "passive"))
      (node (ref "X2") (pin "2") (pinfunction "1_2") (pintype "passive"))
    )
    (net (code "51") (name "RX_DB9") (class "Default")
      (node (ref "K1") (pin "P2") (pinfunction "P_P2") (pintype "passive"))
      (node (ref "K2") (pin "O1") (pinfunction "O_O1") (pintype "passive"))
      (node (ref "MD1") (pin "27") (pinfunction "IO16_27") (pintype "bidirectional"))
      (node (ref "U5") (pin "9") (pinfunction "R2OUT_9") (pintype "output"))
    )
    (net (code "52") (name "RX_DB9-1") (class "Default")
      (node (ref "K1") (pin "S2") (pinfunction "S_S2") (pintype "passive"))
      (node (ref "U2") (pin "9") (pinfunction "R2OUT_9") (pintype "output"))
    )
    (net (code "53") (name "SW_LORACONFIG") (class "Default")
      (node (ref "MD1") (pin "16") (pinfunction "IO13_16") (pintype "bidirectional"))
      (node (ref "R11") (pin "1") (pinfunction "1_1") (pintype "passive"))
    )
    (net (code "54") (name "SW_MODEM") (class "Default")
      (node (ref "MD1") (pin "29") (pinfunction "IO5_29") (pintype "bidirectional"))
      (node (ref "R9") (pin "1") (pinfunction "1_1") (pintype "passive"))
    )
    (net (code "55") (name "T2OUT") (class "Default")
      (node (ref "J1") (pin "2") (pinfunction "2_2") (pintype "passive"))
      (node (ref "U5") (pin "7") (pinfunction "T2OUT_7") (pintype "output"))
    )
    (net (code "56") (name "T2OUT1") (class "Default")
      (node (ref "J2") (pin "2") (pinfunction "2_2") (pintype "passive"))
      (node (ref "U2") (pin "7") (pinfunction "T2OUT_7") (pintype "output"))
    )
    (net (code "57") (name "TX") (class "Default")
      (node (ref "D1") (pin "C") (pinfunction "C_C") (pintype "passive"))
      (node (ref "MD1") (pin "34") (pinfunction "RXD0_34") (pintype "bidirectional"))
      (node (ref "U$2") (pin "2") (pinfunction "TX_2") (pintype "bidirectional"))
    )
    (net (code "58") (name "TXLORA") (class "Default")
      (node (ref "EBYTEE220-900T22D1") (pin "TXD") (pinfunction "TXD_TXD") (pintype "bidirectional"))
      (node (ref "K2") (pin "P1") (pinfunction "P_P1") (pintype "passive"))
    )
    (net (code "59") (name "TXLORA_CONFIG") (class "Default")
      (node (ref "K2") (pin "S1") (pinfunction "S_S1") (pintype "passive"))
      (node (ref "X2") (pin "3") (pinfunction "1_3") (pintype "passive"))
    )
    (net (code "60") (name "TX_DB9") (class "Default")
      (node (ref "D5") (pin "A") (pinfunction "A_A") (pintype "passive"))
      (node (ref "K1") (pin "P1") (pinfunction "P_P1") (pintype "passive"))
      (node (ref "K2") (pin "O2") (pinfunction "O_O2") (pintype "passive"))
      (node (ref "R6") (pin "1") (pinfunction "1_1") (pintype "passive"))
      (node (ref "U5") (pin "10") (pinfunction "T2IN_10") (pintype "input"))
    )
    (net (code "61") (name "TX_DB9-1") (class "Default")
      (node (ref "K1") (pin "S1") (pinfunction "S_S1") (pintype "passive"))
      (node (ref "U2") (pin "10") (pinfunction "T2IN_10") (pintype "input"))
    )
    (net (code "62") (name "USB_N") (class "Default")
      (node (ref "J3") (pin "2") (pinfunction "D-_2") (pintype "bidirectional"))
      (node (ref "U$2") (pin "6") (pinfunction "D-_6") (pintype "bidirectional"))
    )
    (net (code "63") (name "USB_P") (class "Default")
      (node (ref "J3") (pin "3") (pinfunction "D+_3") (pintype "bidirectional"))
      (node (ref "U$2") (pin "5") (pinfunction "D+_5") (pintype "bidirectional"))
    )
    (net (code "64") (name "VUSB") (class "Default")
      (node (ref "C1") (pin "1") (pinfunction "1_1") (pintype "passive"))
      (node (ref "C25") (pin "+") (pinfunction "+_+") (pintype "passive"))
      (node (ref "D3") (pin "A") (pinfunction "A_A") (pintype "passive"))
      (node (ref "J3") (pin "1") (pinfunction "VCC_1") (pintype "power_in"))
      (node (ref "U$2") (pin "16") (pinfunction "VCC_16") (pintype "bidirectional"))
    )
    (net (code "65") (name "unconnected-(EBYTEE220-900T22D1-PadAUX)") (class "Default")
      (node (ref "EBYTEE220-900T22D1") (pin "AUX") (pinfunction "AUX_AUX") (pintype "bidirectional"))
    )
    (net (code "66") (name "unconnected-(J1-Pad1)") (class "Default")
      (node (ref "J1") (pin "1") (pinfunction "1_1") (pintype "passive"))
    )
    (net (code "67") (name "unconnected-(J1-Pad4)") (class "Default")
      (node (ref "J1") (pin "4") (pinfunction "4_4") (pintype "passive"))
    )
    (net (code "68") (name "unconnected-(J1-Pad6)") (class "Default")
      (node (ref "J1") (pin "6") (pinfunction "6_6") (pintype "passive"))
    )
    (net (code "69") (name "unconnected-(J1-Pad7)") (class "Default")
      (node (ref "J1") (pin "7") (pinfunction "7_7") (pintype "passive"))
    )
    (net (code "70") (name "unconnected-(J1-Pad8)") (class "Default")
      (node (ref "J1") (pin "8") (pinfunction "8_8") (pintype "passive"))
    )
    (net (code "71") (name "unconnected-(J1-Pad9)") (class "Default")
      (node (ref "J1") (pin "9") (pinfunction "9_9") (pintype "passive"))
    )
    (net (code "72") (name "unconnected-(J2-Pad1)") (class "Default")
      (node (ref "J2") (pin "1") (pinfunction "1_1") (pintype "passive"))
    )
    (net (code "73") (name "unconnected-(J2-Pad4)") (class "Default")
      (node (ref "J2") (pin "4") (pinfunction "4_4") (pintype "passive"))
    )
    (net (code "74") (name "unconnected-(J2-Pad6)") (class "Default")
      (node (ref "J2") (pin "6") (pinfunction "6_6") (pintype "passive"))
    )
    (net (code "75") (name "unconnected-(J2-Pad7)") (class "Default")
      (node (ref "J2") (pin "7") (pinfunction "7_7") (pintype "passive"))
    )
    (net (code "76") (name "unconnected-(J2-Pad8)") (class "Default")
      (node (ref "J2") (pin "8") (pinfunction "8_8") (pintype "passive"))
    )
    (net (code "77") (name "unconnected-(J2-Pad9)") (class "Default")
      (node (ref "J2") (pin "9") (pinfunction "9_9") (pintype "passive"))
    )
    (net (code "78") (name "unconnected-(J3-ID-Pad4)") (class "Default")
      (node (ref "J3") (pin "4") (pinfunction "ID_4") (pintype "bidirectional"))
    )
    (net (code "79") (name "unconnected-(K1B-O-PadO1)") (class "Default")
      (node (ref "K1") (pin "O1") (pinfunction "O_O1") (pintype "passive"))
    )
    (net (code "80") (name "unconnected-(K1C-O-PadO2)") (class "Default")
      (node (ref "K1") (pin "O2") (pinfunction "O_O2") (pintype "passive"))
    )
    (net (code "81") (name "unconnected-(MD1-CLK-Pad20)") (class "Default")
      (node (ref "MD1") (pin "20") (pinfunction "CLK_20") (pintype "bidirectional"))
    )
    (net (code "82") (name "unconnected-(MD1-CMD-Pad19)") (class "Default")
      (node (ref "MD1") (pin "19") (pinfunction "CMD_19") (pintype "bidirectional"))
    )
    (net (code "83") (name "unconnected-(MD1-IO2-Pad24)") (class "Default")
      (node (ref "MD1") (pin "24") (pinfunction "IO2_24") (pintype "bidirectional"))
    )
    (net (code "84") (name "unconnected-(MD1-IO12-Pad14)") (class "Default")
      (node (ref "MD1") (pin "14") (pinfunction "IO12_14") (pintype "bidirectional"))
    )
    (net (code "85") (name "unconnected-(MD1-IO14-Pad13)") (class "Default")
      (node (ref "MD1") (pin "13") (pinfunction "IO14_13") (pintype "bidirectional"))
    )
    (net (code "86") (name "unconnected-(MD1-IO18-Pad30)") (class "Default")
      (node (ref "MD1") (pin "30") (pinfunction "IO18_30") (pintype "bidirectional"))
    )
    (net (code "87") (name "unconnected-(MD1-IO19-Pad31)") (class "Default")
      (node (ref "MD1") (pin "31") (pinfunction "IO19_31") (pintype "bidirectional"))
    )
    (net (code "88") (name "unconnected-(MD1-IO21-Pad33)") (class "Default")
      (node (ref "MD1") (pin "33") (pinfunction "IO21_33") (pintype "bidirectional"))
    )
    (net (code "89") (name "unconnected-(MD1-IO22-Pad36)") (class "Default")
      (node (ref "MD1") (pin "36") (pinfunction "IO22_36") (pintype "bidirectional"))
    )
    (net (code "90") (name "unconnected-(MD1-IO23-Pad37)") (class "Default")
      (node (ref "MD1") (pin "37") (pinfunction "IO23_37") (pintype "bidirectional"))
    )
    (net (code "91") (name "unconnected-(MD1-IO25-Pad10)") (class "Default")
      (node (ref "MD1") (pin "10") (pinfunction "IO25_10") (pintype "bidirectional"))
    )
    (net (code "92") (name "unconnected-(MD1-IO26-Pad11)") (class "Default")
      (node (ref "MD1") (pin "11") (pinfunction "IO26_11") (pintype "bidirectional"))
    )
    (net (code "93") (name "unconnected-(MD1-IO32-Pad8)") (class "Default")
      (node (ref "MD1") (pin "8") (pinfunction "IO32_8") (pintype "bidirectional"))
    )
    (net (code "94") (name "unconnected-(MD1-IO33-Pad9)") (class "Default")
      (node (ref "MD1") (pin "9") (pinfunction "IO33_9") (pintype "bidirectional"))
    )
    (net (code "95") (name "unconnected-(MD1-IO34-Pad6)") (class "Default")
      (node (ref "MD1") (pin "6") (pinfunction "IO34_6") (pintype "bidirectional"))
    )
    (net (code "96") (name "unconnected-(MD1-IO35-Pad7)") (class "Default")
      (node (ref "MD1") (pin "7") (pinfunction "IO35_7") (pintype "bidirectional"))
    )
    (net (code "97") (name "unconnected-(MD1-NC-Pad32)") (class "Default")
      (node (ref "MD1") (pin "32") (pinfunction "NC_32") (pintype "passive"))
    )
    (net (code "98") (name "unconnected-(MD1-SD0-Pad21)") (class "Default")
      (node (ref "MD1") (pin "21") (pinfunction "SD0_21") (pintype "bidirectional"))
    )
    (net (code "99") (name "unconnected-(MD1-SD1-Pad22)") (class "Default")
      (node (ref "MD1") (pin "22") (pinfunction "SD1_22") (pintype "bidirectional"))
    )
    (net (code "100") (name "unconnected-(MD1-SD2-Pad17)") (class "Default")
      (node (ref "MD1") (pin "17") (pinfunction "SD2_17") (pintype "bidirectional"))
    )
    (net (code "101") (name "unconnected-(MD1-SD3-Pad18)") (class "Default")
      (node (ref "MD1") (pin "18") (pinfunction "SD3_18") (pintype "bidirectional"))
    )
    (net (code "102") (name "unconnected-(MD1-SENSOR_VN-Pad5)") (class "Default")
      (node (ref "MD1") (pin "5") (pinfunction "SENSOR_VN_5") (pintype "input"))
    )
    (net (code "103") (name "unconnected-(MD1-SENSOR_VP-Pad4)") (class "Default")
      (node (ref "MD1") (pin "4") (pinfunction "SENSOR_VP_4") (pintype "input"))
    )
    (net (code "104") (name "unconnected-(U$2-CTS-Pad9)") (class "Default")
      (node (ref "U$2") (pin "9") (pinfunction "CTS_9") (pintype "bidirectional"))
    )
    (net (code "105") (name "unconnected-(U$2-DCD-Pad12)") (class "Default")
      (node (ref "U$2") (pin "12") (pinfunction "DCD_12") (pintype "bidirectional"))
    )
    (net (code "106") (name "unconnected-(U$2-DSR-Pad10)") (class "Default")
      (node (ref "U$2") (pin "10") (pinfunction "DSR_10") (pintype "bidirectional"))
    )
    (net (code "107") (name "unconnected-(U$2-RI-Pad11)") (class "Default")
      (node (ref "U$2") (pin "11") (pinfunction "RI_11") (pintype "bidirectional"))
    )
    (net (code "108") (name "unconnected-(U$2-RS232-Pad15)") (class "Default")
      (node (ref "U$2") (pin "15") (pinfunction "RS232_15") (pintype "bidirectional"))
    )
    (net (code "109") (name "unconnected-(U2-R1IN-Pad13)") (class "Default")
      (node (ref "U2") (pin "13") (pinfunction "R1IN_13") (pintype "input"))
    )
    (net (code "110") (name "unconnected-(U2-R1OUT-Pad12)") (class "Default")
      (node (ref "U2") (pin "12") (pinfunction "R1OUT_12") (pintype "output"))
    )
    (net (code "111") (name "unconnected-(U2-T1IN-Pad11)") (class "Default")
      (node (ref "U2") (pin "11") (pinfunction "T1IN_11") (pintype "input"))
    )
    (net (code "112") (name "unconnected-(U2-T1OUT-Pad14)") (class "Default")
      (node (ref "U2") (pin "14") (pinfunction "T1OUT_14") (pintype "output"))
    )
    (net (code "113") (name "unconnected-(U5-R1IN-Pad13)") (class "Default")
      (node (ref "U5") (pin "13") (pinfunction "R1IN_13") (pintype "input"))
    )
    (net (code "114") (name "unconnected-(U5-R1OUT-Pad12)") (class "Default")
      (node (ref "U5") (pin "12") (pinfunction "R1OUT_12") (pintype "output"))
    )
    (net (code "115") (name "unconnected-(U5-T1IN-Pad11)") (class "Default")
      (node (ref "U5") (pin "11") (pinfunction "T1IN_11") (pintype "input"))
    )
    (net (code "116") (name "unconnected-(U5-T1OUT-Pad14)") (class "Default")
      (node (ref "U5") (pin "14") (pinfunction "T1OUT_14") (pintype "output"))
    )
  )
)
